# isp.net
KiCad netlist of a schematic drawn in EAGLE
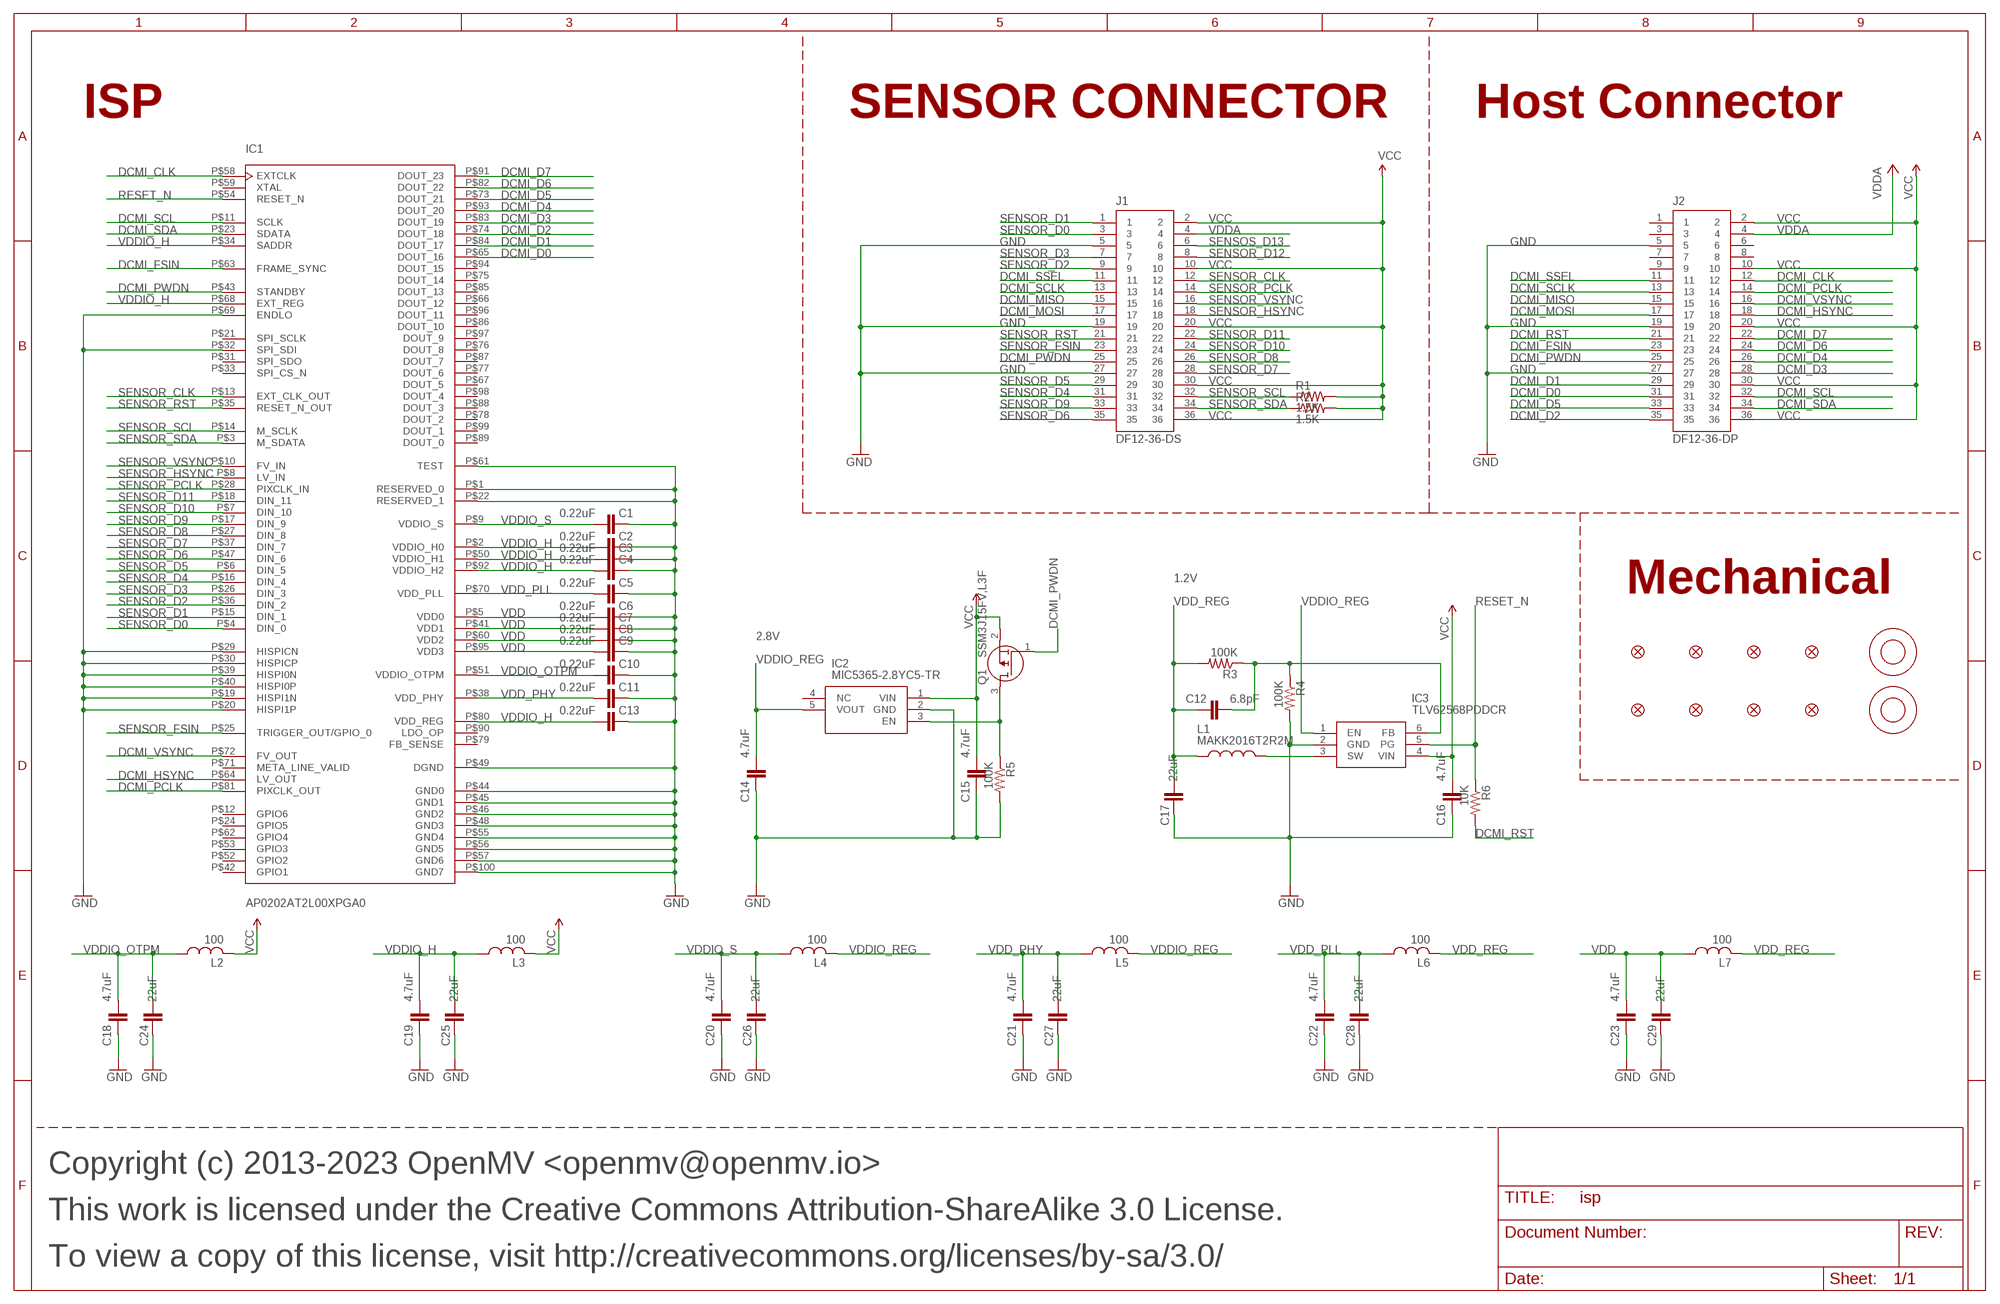
[diagram p0: schematic, sheet 1]

(export (version "E")
  (design (tool "Eeschema 10.0.6"))
  (components
    (comp (ref "C1")
      (value "0.22uF")
      (footprint "eagle-import:C0201")
      (fields (field (name "MPN") "GRM033R60J224ME15D"))
      (libsource (lib "eagle-import") (part "C-EUC0201"))
    )
    (comp (ref "C2")
      (value "0.22uF")
      (footprint "eagle-import:C0201")
      (fields (field (name "MPN") "GRM033R60J224ME15D"))
      (libsource (lib "eagle-import") (part "C-EUC0201"))
    )
    (comp (ref "C3")
      (value "0.22uF")
      (footprint "eagle-import:C0201")
      (fields (field (name "MPN") "GRM033R60J224ME15D"))
      (libsource (lib "eagle-import") (part "C-EUC0201"))
    )
    (comp (ref "C4")
      (value "0.22uF")
      (footprint "eagle-import:C0201")
      (fields (field (name "MPN") "GRM033R60J224ME15D"))
      (libsource (lib "eagle-import") (part "C-EUC0201"))
    )
    (comp (ref "C5")
      (value "0.22uF")
      (footprint "eagle-import:C0201")
      (fields (field (name "MPN") "GRM033R60J224ME15D"))
      (libsource (lib "eagle-import") (part "C-EUC0201"))
    )
    (comp (ref "C6")
      (value "0.22uF")
      (footprint "eagle-import:C0201")
      (fields (field (name "MPN") "GRM033R60J224ME15D"))
      (libsource (lib "eagle-import") (part "C-EUC0201"))
    )
    (comp (ref "C7")
      (value "0.22uF")
      (footprint "eagle-import:C0201")
      (fields (field (name "MPN") "GRM033R60J224ME15D"))
      (libsource (lib "eagle-import") (part "C-EUC0201"))
    )
    (comp (ref "C8")
      (value "0.22uF")
      (footprint "eagle-import:C0201")
      (fields (field (name "MPN") "GRM033R60J224ME15D"))
      (libsource (lib "eagle-import") (part "C-EUC0201"))
    )
    (comp (ref "C9")
      (value "0.22uF")
      (footprint "eagle-import:C0201")
      (fields (field (name "MPN") "GRM033R60J224ME15D"))
      (libsource (lib "eagle-import") (part "C-EUC0201"))
    )
    (comp (ref "C10")
      (value "0.22uF")
      (footprint "eagle-import:C0201")
      (fields (field (name "MPN") "GRM033R60J224ME15D"))
      (libsource (lib "eagle-import") (part "C-EUC0201"))
    )
    (comp (ref "C11")
      (value "0.22uF")
      (footprint "eagle-import:C0201")
      (fields (field (name "MPN") "GRM033R60J224ME15D"))
      (libsource (lib "eagle-import") (part "C-EUC0201"))
    )
    (comp (ref "C12")
      (value "6.8pF")
      (footprint "eagle-import:0402")
      (fields (field (name "MPN") "GRM1555C1H6R8DA01D"))
      (libsource (lib "eagle-import") (part "CAP_0402"))
    )
    (comp (ref "C13")
      (value "0.22uF")
      (footprint "eagle-import:C0201")
      (fields (field (name "MPN") "GRM033R60J224ME15D"))
      (libsource (lib "eagle-import") (part "C-EUC0201"))
    )
    (comp (ref "C14")
      (value "4.7uF")
      (footprint "eagle-import:0402")
      (fields (field (name "MPN") "JMK105BBJ475MV-F"))
      (libsource (lib "eagle-import") (part "CAP_0402"))
    )
    (comp (ref "C15")
      (value "4.7uF")
      (footprint "eagle-import:0402")
      (fields (field (name "MPN") "JMK105BBJ475MV-F"))
      (libsource (lib "eagle-import") (part "CAP_0402"))
    )
    (comp (ref "C16")
      (value "4.7uF")
      (footprint "eagle-import:0402")
      (fields (field (name "MPN") "JMK105BBJ475MV-F"))
      (libsource (lib "eagle-import") (part "CAP_0402"))
    )
    (comp (ref "C17")
      (value "22uF")
      (footprint "eagle-import:0805")
      (fields (field (name "MPN") "CL21A226MQQNNNE"))
      (libsource (lib "eagle-import") (part "22UF-0805-6.3V-20%"))
    )
    (comp (ref "C18")
      (value "4.7uF")
      (footprint "eagle-import:0402")
      (fields (field (name "MPN") "JMK105BBJ475MV-F"))
      (libsource (lib "eagle-import") (part "CAP_0402"))
    )
    (comp (ref "C19")
      (value "4.7uF")
      (footprint "eagle-import:0402")
      (fields (field (name "MPN") "JMK105BBJ475MV-F"))
      (libsource (lib "eagle-import") (part "CAP_0402"))
    )
    (comp (ref "C20")
      (value "4.7uF")
      (footprint "eagle-import:0402")
      (fields (field (name "MPN") "JMK105BBJ475MV-F"))
      (libsource (lib "eagle-import") (part "CAP_0402"))
    )
    (comp (ref "C21")
      (value "4.7uF")
      (footprint "eagle-import:0402")
      (fields (field (name "MPN") "JMK105BBJ475MV-F"))
      (libsource (lib "eagle-import") (part "CAP_0402"))
    )
    (comp (ref "C22")
      (value "4.7uF")
      (footprint "eagle-import:0402")
      (fields (field (name "MPN") "JMK105BBJ475MV-F"))
      (libsource (lib "eagle-import") (part "CAP_0402"))
    )
    (comp (ref "C23")
      (value "4.7uF")
      (footprint "eagle-import:0402")
      (fields (field (name "MPN") "JMK105BBJ475MV-F"))
      (libsource (lib "eagle-import") (part "CAP_0402"))
    )
    (comp (ref "C24")
      (value "22uF")
      (footprint "eagle-import:0805")
      (fields (field (name "MPN") "CL21A226MQQNNNE"))
      (libsource (lib "eagle-import") (part "22UF-0805-6.3V-20%"))
    )
    (comp (ref "C25")
      (value "22uF")
      (footprint "eagle-import:0805")
      (fields (field (name "MPN") "CL21A226MQQNNNE"))
      (libsource (lib "eagle-import") (part "22UF-0805-6.3V-20%"))
    )
    (comp (ref "C26")
      (value "22uF")
      (footprint "eagle-import:0805")
      (fields (field (name "MPN") "CL21A226MQQNNNE"))
      (libsource (lib "eagle-import") (part "22UF-0805-6.3V-20%"))
    )
    (comp (ref "C27")
      (value "22uF")
      (footprint "eagle-import:0805")
      (fields (field (name "MPN") "CL21A226MQQNNNE"))
      (libsource (lib "eagle-import") (part "22UF-0805-6.3V-20%"))
    )
    (comp (ref "C28")
      (value "22uF")
      (footprint "eagle-import:0805")
      (fields (field (name "MPN") "CL21A226MQQNNNE"))
      (libsource (lib "eagle-import") (part "22UF-0805-6.3V-20%"))
    )
    (comp (ref "C29")
      (value "22uF")
      (footprint "eagle-import:0805")
      (fields (field (name "MPN") "CL21A226MQQNNNE"))
      (libsource (lib "eagle-import") (part "22UF-0805-6.3V-20%"))
    )
    (comp (ref "FD1")
      (value "FIDUCIAL1X2")
      (footprint "eagle-import:FIDUCIAL-1X2")
      (libsource (lib "eagle-import") (part "FIDUCIAL1X2"))
    )
    (comp (ref "FD2")
      (value "FIDUCIAL1X2")
      (footprint "eagle-import:FIDUCIAL-1X2")
      (libsource (lib "eagle-import") (part "FIDUCIAL1X2"))
    )
    (comp (ref "FD3")
      (value "FIDUCIAL1X2")
      (footprint "eagle-import:FIDUCIAL-1X2")
      (libsource (lib "eagle-import") (part "FIDUCIAL1X2"))
    )
    (comp (ref "FD4")
      (value "FIDUCIAL1X2")
      (footprint "eagle-import:FIDUCIAL-1X2")
      (libsource (lib "eagle-import") (part "FIDUCIAL1X2"))
    )
    (comp (ref "FD5")
      (value "FIDUCIAL1X2")
      (footprint "eagle-import:FIDUCIAL-1X2")
      (libsource (lib "eagle-import") (part "FIDUCIAL1X2"))
    )
    (comp (ref "FD6")
      (value "FIDUCIAL1X2")
      (footprint "eagle-import:FIDUCIAL-1X2")
      (libsource (lib "eagle-import") (part "FIDUCIAL1X2"))
    )
    (comp (ref "FD7")
      (value "FIDUCIAL1X2")
      (footprint "eagle-import:FIDUCIAL-1X2")
      (libsource (lib "eagle-import") (part "FIDUCIAL1X2"))
    )
    (comp (ref "FD8")
      (value "FIDUCIAL1X2")
      (footprint "eagle-import:FIDUCIAL-1X2")
      (libsource (lib "eagle-import") (part "FIDUCIAL1X2"))
    )
    (comp (ref "IC1")
      (value "AP0202AT2L00XPGA0")
      (footprint "eagle-import:AP0202AT2L00XPGA0")
      (fields (field (name "MPN") "AP0202AT2L00XPGA0-DR"))
      (libsource (lib "eagle-import") (part "AP0202AT2L00XPGA0"))
    )
    (comp (ref "IC2")
      (value "MIC5365-2.8YC5-TR")
      (footprint "eagle-import:SOT65P210X110-5N")
      (fields (field (name "MOUSER_PART_NUMBER") "998-MIC5365-2.8YC5TR"))
      (libsource (lib "eagle-import") (part "MIC5365-2.8YC5-TR"))
    )
    (comp (ref "IC3")
      (value "TLV62568PDDCR")
      (footprint "eagle-import:SOT95P280X110-6N")
      (fields (field (name "MOUSER_PART_NUMBER") "595-TLV62568PDDCR"))
      (libsource (lib "eagle-import") (part "TLV62568PDDCR"))
    )
    (comp (ref "J1")
      (value "DF12-36-DS")
      (footprint "eagle-import:DF12-36-DS")
      (fields (field (name "MPN") "DF12NB(3.0)-36DS-0.5V(51)"))
      (libsource (lib "eagle-import") (part "DF12-36-DS"))
    )
    (comp (ref "J2")
      (value "DF12-36-DP")
      (footprint "eagle-import:DF12-36-DP")
      (fields (field (name "MPN") "DF12NB(3.0)-36DP-0.5V(51)"))
      (libsource (lib "eagle-import") (part "DF12-36-DP"))
    )
    (comp (ref "L1")
      (value "MAKK2016T2R2M")
      (footprint "eagle-import:INDC2016X100N")
      (fields (field (name "MF") "Taiyo Yuden"))
      (libsource (lib "eagle-import") (part "MAKK2016T2R2M"))
    )
    (comp (ref "L2")
      (value "100")
      (footprint "eagle-import:0402")
      (fields (field (name "MPN") "MFBM1V1005-101-R"))
      (libsource (lib "eagle-import") (part "INDUCTOR_0402"))
    )
    (comp (ref "L3")
      (value "100")
      (footprint "eagle-import:0402")
      (fields (field (name "MPN") "MFBM1V1005-101-R"))
      (libsource (lib "eagle-import") (part "INDUCTOR_0402"))
    )
    (comp (ref "L4")
      (value "100")
      (footprint "eagle-import:0402")
      (fields (field (name "MPN") "MFBM1V1005-101-R"))
      (libsource (lib "eagle-import") (part "INDUCTOR_0402"))
    )
    (comp (ref "L5")
      (value "100")
      (footprint "eagle-import:0402")
      (fields (field (name "MPN") "MFBM1V1005-101-R"))
      (libsource (lib "eagle-import") (part "INDUCTOR_0402"))
    )
    (comp (ref "L6")
      (value "100")
      (footprint "eagle-import:0402")
      (fields (field (name "MPN") "MFBM1V1005-101-R"))
      (libsource (lib "eagle-import") (part "INDUCTOR_0402"))
    )
    (comp (ref "L7")
      (value "100")
      (footprint "eagle-import:0402")
      (fields (field (name "MPN") "MFBM1V1005-101-R"))
      (libsource (lib "eagle-import") (part "INDUCTOR_0402"))
    )
    (comp (ref "M1")
      (value "9774030151R")
      (footprint "eagle-import:9774030151R")
      (libsource (lib "eagle-import") (part "9774030151R"))
    )
    (comp (ref "M2")
      (value "9774030151R")
      (footprint "eagle-import:9774030151R")
      (libsource (lib "eagle-import") (part "9774030151R"))
    )
    (comp (ref "Q1")
      (value "SSM3J15FV,L3F")
      (footprint "eagle-import:SSM3J15FVL3F")
      (fields (field (name "MOUSER_PART_NUMBER") "757-SSM3J15FVL3F"))
      (libsource (lib "eagle-import") (part "SSM3J15FV,L3F"))
    )
    (comp (ref "R1")
      (value "1.5K")
      (footprint "eagle-import:R0402")
      (fields (field (name "MPN") "RC0402FR-131K5L"))
      (libsource (lib "eagle-import") (part "R-US_R0402"))
    )
    (comp (ref "R2")
      (value "1.5K")
      (footprint "eagle-import:R0402")
      (fields (field (name "MPN") "RC0402FR-131K5L"))
      (libsource (lib "eagle-import") (part "R-US_R0402"))
    )
    (comp (ref "R3")
      (value "100K")
      (footprint "eagle-import:R0402")
      (fields (field (name "MPN") "AC0402FR-07100KL"))
      (libsource (lib "eagle-import") (part "R-US_R0402"))
    )
    (comp (ref "R4")
      (value "100K")
      (footprint "eagle-import:R0402")
      (fields (field (name "MPN") "AC0402FR-07100KL"))
      (libsource (lib "eagle-import") (part "R-US_R0402"))
    )
    (comp (ref "R5")
      (value "100K")
      (footprint "eagle-import:R0402")
      (fields (field (name "MPN") "AC0402FR-07100KL"))
      (libsource (lib "eagle-import") (part "R-US_R0402"))
    )
    (comp (ref "R6")
      (value "10K")
      (footprint "eagle-import:R0402")
      (fields (field (name "MPN") "AC0402FR-1310KL"))
      (libsource (lib "eagle-import") (part "R-US_R0402"))
    )
  )
  (nets
    (net (code "1") (name "/DCMI_CLK") (class "Default")
      (node (ref "IC1") (pin "P$58") (pinfunction "EXTCLK_P$58") (pintype "input"))
      (node (ref "J2") (pin "12") (pinfunction "12_12") (pintype "bidirectional"))
    )
    (net (code "2") (name "/DCMI_D0") (class "Default")
      (node (ref "IC1") (pin "P$65") (pinfunction "DOUT_16_P$65") (pintype "output"))
      (node (ref "J2") (pin "31") (pinfunction "31_31") (pintype "bidirectional"))
    )
    (net (code "3") (name "/DCMI_D1") (class "Default")
      (node (ref "IC1") (pin "P$84") (pinfunction "DOUT_17_P$84") (pintype "output"))
      (node (ref "J2") (pin "29") (pinfunction "29_29") (pintype "bidirectional"))
    )
    (net (code "4") (name "/DCMI_D2") (class "Default")
      (node (ref "IC1") (pin "P$74") (pinfunction "DOUT_18_P$74") (pintype "output"))
      (node (ref "J2") (pin "35") (pinfunction "35_35") (pintype "bidirectional"))
    )
    (net (code "5") (name "/DCMI_D3") (class "Default")
      (node (ref "IC1") (pin "P$83") (pinfunction "DOUT_19_P$83") (pintype "output"))
      (node (ref "J2") (pin "28") (pinfunction "28_28") (pintype "bidirectional"))
    )
    (net (code "6") (name "/DCMI_D4") (class "Default")
      (node (ref "IC1") (pin "P$93") (pinfunction "DOUT_20_P$93") (pintype "output"))
      (node (ref "J2") (pin "26") (pinfunction "26_26") (pintype "bidirectional"))
    )
    (net (code "7") (name "/DCMI_D5") (class "Default")
      (node (ref "IC1") (pin "P$73") (pinfunction "DOUT_21_P$73") (pintype "output"))
      (node (ref "J2") (pin "33") (pinfunction "33_33") (pintype "bidirectional"))
    )
    (net (code "8") (name "/DCMI_D6") (class "Default")
      (node (ref "IC1") (pin "P$82") (pinfunction "DOUT_22_P$82") (pintype "output"))
      (node (ref "J2") (pin "24") (pinfunction "24_24") (pintype "bidirectional"))
    )
    (net (code "9") (name "/DCMI_D7") (class "Default")
      (node (ref "IC1") (pin "P$91") (pinfunction "DOUT_23_P$91") (pintype "output"))
      (node (ref "J2") (pin "22") (pinfunction "22_22") (pintype "bidirectional"))
    )
    (net (code "10") (name "/DCMI_FSIN") (class "Default")
      (node (ref "IC1") (pin "P$63") (pinfunction "FRAME_SYNC_P$63") (pintype "input"))
      (node (ref "J2") (pin "23") (pinfunction "23_23") (pintype "bidirectional"))
    )
    (net (code "11") (name "/DCMI_HSYNC") (class "Default")
      (node (ref "IC1") (pin "P$64") (pinfunction "LV_OUT_P$64") (pintype "output"))
      (node (ref "J2") (pin "18") (pinfunction "18_18") (pintype "bidirectional"))
    )
    (net (code "12") (name "/DCMI_MISO") (class "Default")
      (node (ref "J1") (pin "15") (pinfunction "15_15") (pintype "bidirectional"))
      (node (ref "J2") (pin "15") (pinfunction "15_15") (pintype "bidirectional"))
    )
    (net (code "13") (name "/DCMI_MOSI") (class "Default")
      (node (ref "J1") (pin "17") (pinfunction "17_17") (pintype "bidirectional"))
      (node (ref "J2") (pin "17") (pinfunction "17_17") (pintype "bidirectional"))
    )
    (net (code "14") (name "/DCMI_PCLK") (class "Default")
      (node (ref "IC1") (pin "P$81") (pinfunction "PIXCLK_OUT_P$81") (pintype "output"))
      (node (ref "J2") (pin "14") (pinfunction "14_14") (pintype "bidirectional"))
    )
    (net (code "15") (name "/DCMI_PWDN") (class "Default")
      (node (ref "IC1") (pin "P$43") (pinfunction "STANDBY_P$43") (pintype "input"))
      (node (ref "J1") (pin "25") (pinfunction "25_25") (pintype "bidirectional"))
      (node (ref "J2") (pin "25") (pinfunction "25_25") (pintype "bidirectional"))
      (node (ref "Q1") (pin "1") (pinfunction "G_1") (pintype "bidirectional"))
    )
    (net (code "16") (name "/DCMI_RST") (class "Default")
      (node (ref "J2") (pin "21") (pinfunction "21_21") (pintype "bidirectional"))
      (node (ref "R6") (pin "2") (pinfunction "2_2") (pintype "passive"))
    )
    (net (code "17") (name "/DCMI_SCL") (class "Default")
      (node (ref "IC1") (pin "P$11") (pinfunction "SCLK_P$11") (pintype "input"))
      (node (ref "J2") (pin "32") (pinfunction "32_32") (pintype "bidirectional"))
    )
    (net (code "18") (name "/DCMI_SCLK") (class "Default")
      (node (ref "J1") (pin "13") (pinfunction "13_13") (pintype "bidirectional"))
      (node (ref "J2") (pin "13") (pinfunction "13_13") (pintype "bidirectional"))
    )
    (net (code "19") (name "/DCMI_SDA") (class "Default")
      (node (ref "IC1") (pin "P$23") (pinfunction "SDATA_P$23") (pintype "bidirectional"))
      (node (ref "J2") (pin "34") (pinfunction "34_34") (pintype "bidirectional"))
    )
    (net (code "20") (name "/DCMI_SSEL") (class "Default")
      (node (ref "J1") (pin "11") (pinfunction "11_11") (pintype "bidirectional"))
      (node (ref "J2") (pin "11") (pinfunction "11_11") (pintype "bidirectional"))
    )
    (net (code "21") (name "/DCMI_VSYNC") (class "Default")
      (node (ref "IC1") (pin "P$72") (pinfunction "FV_OUT_P$72") (pintype "output"))
      (node (ref "J2") (pin "16") (pinfunction "16_16") (pintype "bidirectional"))
    )
    (net (code "22") (name "/RESET_N") (class "Default")
      (node (ref "IC1") (pin "P$54") (pinfunction "RESET_N_P$54") (pintype "input"))
      (node (ref "IC3") (pin "5") (pinfunction "PG_5") (pintype "bidirectional"))
      (node (ref "R6") (pin "1") (pinfunction "1_1") (pintype "passive"))
    )
    (net (code "23") (name "/SENSOR_CLK") (class "Default")
      (node (ref "IC1") (pin "P$13") (pinfunction "EXT_CLK_OUT_P$13") (pintype "output"))
      (node (ref "J1") (pin "12") (pinfunction "12_12") (pintype "bidirectional"))
    )
    (net (code "24") (name "/SENSOR_D0") (class "Default")
      (node (ref "IC1") (pin "P$4") (pinfunction "DIN_0_P$4") (pintype "input"))
      (node (ref "J1") (pin "3") (pinfunction "3_3") (pintype "bidirectional"))
    )
    (net (code "25") (name "/SENSOR_D1") (class "Default")
      (node (ref "IC1") (pin "P$15") (pinfunction "DIN_1_P$15") (pintype "input"))
      (node (ref "J1") (pin "1") (pinfunction "1_1") (pintype "bidirectional"))
    )
    (net (code "26") (name "/SENSOR_D2") (class "Default")
      (node (ref "IC1") (pin "P$36") (pinfunction "DIN_2_P$36") (pintype "input"))
      (node (ref "J1") (pin "9") (pinfunction "9_9") (pintype "bidirectional"))
    )
    (net (code "27") (name "/SENSOR_D3") (class "Default")
      (node (ref "IC1") (pin "P$26") (pinfunction "DIN_3_P$26") (pintype "input"))
      (node (ref "J1") (pin "7") (pinfunction "7_7") (pintype "bidirectional"))
    )
    (net (code "28") (name "/SENSOR_D4") (class "Default")
      (node (ref "IC1") (pin "P$16") (pinfunction "DIN_4_P$16") (pintype "input"))
      (node (ref "J1") (pin "31") (pinfunction "31_31") (pintype "bidirectional"))
    )
    (net (code "29") (name "/SENSOR_D5") (class "Default")
      (node (ref "IC1") (pin "P$6") (pinfunction "DIN_5_P$6") (pintype "input"))
      (node (ref "J1") (pin "29") (pinfunction "29_29") (pintype "bidirectional"))
    )
    (net (code "30") (name "/SENSOR_D6") (class "Default")
      (node (ref "IC1") (pin "P$47") (pinfunction "DIN_6_P$47") (pintype "input"))
      (node (ref "J1") (pin "35") (pinfunction "35_35") (pintype "bidirectional"))
    )
    (net (code "31") (name "/SENSOR_D7") (class "Default")
      (node (ref "IC1") (pin "P$37") (pinfunction "DIN_7_P$37") (pintype "input"))
      (node (ref "J1") (pin "28") (pinfunction "28_28") (pintype "bidirectional"))
    )
    (net (code "32") (name "/SENSOR_D8") (class "Default")
      (node (ref "IC1") (pin "P$27") (pinfunction "DIN_8_P$27") (pintype "input"))
      (node (ref "J1") (pin "26") (pinfunction "26_26") (pintype "bidirectional"))
    )
    (net (code "33") (name "/SENSOR_D9") (class "Default")
      (node (ref "IC1") (pin "P$17") (pinfunction "DIN_9_P$17") (pintype "input"))
      (node (ref "J1") (pin "33") (pinfunction "33_33") (pintype "bidirectional"))
    )
    (net (code "34") (name "/SENSOR_D10") (class "Default")
      (node (ref "IC1") (pin "P$7") (pinfunction "DIN_10_P$7") (pintype "input"))
      (node (ref "J1") (pin "24") (pinfunction "24_24") (pintype "bidirectional"))
    )
    (net (code "35") (name "/SENSOR_D11") (class "Default")
      (node (ref "IC1") (pin "P$18") (pinfunction "DIN_11_P$18") (pintype "input"))
      (node (ref "J1") (pin "22") (pinfunction "22_22") (pintype "bidirectional"))
    )
    (net (code "36") (name "/SENSOR_D12") (class "Default")
      (node (ref "J1") (pin "8") (pinfunction "8_8") (pintype "bidirectional"))
    )
    (net (code "37") (name "/SENSOR_FSIN") (class "Default")
      (node (ref "IC1") (pin "P$25") (pinfunction "TRIGGER_OUT/GPIO_0_P$25") (pintype "output"))
      (node (ref "J1") (pin "23") (pinfunction "23_23") (pintype "bidirectional"))
    )
    (net (code "38") (name "/SENSOR_HSYNC") (class "Default")
      (node (ref "IC1") (pin "P$8") (pinfunction "LV_IN_P$8") (pintype "input"))
      (node (ref "J1") (pin "18") (pinfunction "18_18") (pintype "bidirectional"))
    )
    (net (code "39") (name "/SENSOR_PCLK") (class "Default")
      (node (ref "IC1") (pin "P$28") (pinfunction "PIXCLK_IN_P$28") (pintype "input"))
      (node (ref "J1") (pin "14") (pinfunction "14_14") (pintype "bidirectional"))
    )
    (net (code "40") (name "/SENSOR_RST") (class "Default")
      (node (ref "IC1") (pin "P$35") (pinfunction "RESET_N_OUT_P$35") (pintype "output"))
      (node (ref "J1") (pin "21") (pinfunction "21_21") (pintype "bidirectional"))
    )
    (net (code "41") (name "/SENSOR_SCL") (class "Default")
      (node (ref "IC1") (pin "P$14") (pinfunction "M_SCLK_P$14") (pintype "output"))
      (node (ref "J1") (pin "32") (pinfunction "32_32") (pintype "bidirectional"))
      (node (ref "R1") (pin "1") (pinfunction "1_1") (pintype "passive"))
    )
    (net (code "42") (name "/SENSOR_SDA") (class "Default")
      (node (ref "IC1") (pin "P$3") (pinfunction "M_SDATA_P$3") (pintype "bidirectional"))
      (node (ref "J1") (pin "34") (pinfunction "34_34") (pintype "bidirectional"))
      (node (ref "R2") (pin "1") (pinfunction "1_1") (pintype "passive"))
    )
    (net (code "43") (name "/SENSOR_VSYNC") (class "Default")
      (node (ref "IC1") (pin "P$10") (pinfunction "FV_IN_P$10") (pintype "input"))
      (node (ref "J1") (pin "16") (pinfunction "16_16") (pintype "bidirectional"))
    )
    (net (code "44") (name "/SENSOS_D13") (class "Default")
      (node (ref "J1") (pin "6") (pinfunction "6_6") (pintype "bidirectional"))
    )
    (net (code "45") (name "/VDD") (class "Default")
      (node (ref "C23") (pin "2") (pinfunction "2_2") (pintype "passive"))
      (node (ref "C29") (pin "2") (pinfunction "2_2") (pintype "passive"))
      (node (ref "C6") (pin "2") (pinfunction "2_2") (pintype "passive"))
      (node (ref "C7") (pin "2") (pinfunction "2_2") (pintype "passive"))
      (node (ref "C8") (pin "2") (pinfunction "2_2") (pintype "passive"))
      (node (ref "C9") (pin "2") (pinfunction "2_2") (pintype "passive"))
      (node (ref "IC1") (pin "P$41") (pinfunction "VDD1_P$41") (pintype "power_in"))
      (node (ref "IC1") (pin "P$5") (pinfunction "VDD0_P$5") (pintype "power_in"))
      (node (ref "IC1") (pin "P$60") (pinfunction "VDD2_P$60") (pintype "power_in"))
      (node (ref "IC1") (pin "P$95") (pinfunction "VDD3_P$95") (pintype "power_in"))
      (node (ref "L7") (pin "1") (pinfunction "P$1_1") (pintype "passive"))
    )
    (net (code "46") (name "/VDDIO_H") (class "Default")
      (node (ref "C13") (pin "2") (pinfunction "2_2") (pintype "passive"))
      (node (ref "C19") (pin "2") (pinfunction "2_2") (pintype "passive"))
      (node (ref "C2") (pin "2") (pinfunction "2_2") (pintype "passive"))
      (node (ref "C25") (pin "2") (pinfunction "2_2") (pintype "passive"))
      (node (ref "C3") (pin "2") (pinfunction "2_2") (pintype "passive"))
      (node (ref "C4") (pin "2") (pinfunction "2_2") (pintype "passive"))
      (node (ref "IC1") (pin "P$2") (pinfunction "VDDIO_H0_P$2") (pintype "power_in"))
      (node (ref "IC1") (pin "P$34") (pinfunction "SADDR_P$34") (pintype "input"))
      (node (ref "IC1") (pin "P$50") (pinfunction "VDDIO_H1_P$50") (pintype "power_in"))
      (node (ref "IC1") (pin "P$68") (pinfunction "EXT_REG_P$68") (pintype "input"))
      (node (ref "IC1") (pin "P$80") (pinfunction "VDD_REG_P$80") (pintype "power_in"))
      (node (ref "IC1") (pin "P$92") (pinfunction "VDDIO_H2_P$92") (pintype "power_in"))
      (node (ref "L3") (pin "1") (pinfunction "P$1_1") (pintype "passive"))
    )
    (net (code "47") (name "/VDDIO_OTPM") (class "Default")
      (node (ref "C10") (pin "2") (pinfunction "2_2") (pintype "passive"))
      (node (ref "C18") (pin "2") (pinfunction "2_2") (pintype "passive"))
      (node (ref "C24") (pin "2") (pinfunction "2_2") (pintype "passive"))
      (node (ref "IC1") (pin "P$51") (pinfunction "VDDIO_OTPM_P$51") (pintype "power_in"))
      (node (ref "L2") (pin "1") (pinfunction "P$1_1") (pintype "passive"))
    )
    (net (code "48") (name "/VDDIO_REG") (class "Default")
      (node (ref "C14") (pin "2") (pinfunction "2_2") (pintype "passive"))
      (node (ref "IC2") (pin "5") (pinfunction "VOUT_5") (pintype "bidirectional"))
      (node (ref "IC3") (pin "1") (pinfunction "EN_1") (pintype "bidirectional"))
      (node (ref "L4") (pin "2") (pinfunction "P$2_2") (pintype "passive"))
      (node (ref "L5") (pin "2") (pinfunction "P$2_2") (pintype "passive"))
    )
    (net (code "49") (name "/VDDIO_S") (class "Default")
      (node (ref "C1") (pin "2") (pinfunction "2_2") (pintype "passive"))
      (node (ref "C20") (pin "2") (pinfunction "2_2") (pintype "passive"))
      (node (ref "C26") (pin "2") (pinfunction "2_2") (pintype "passive"))
      (node (ref "IC1") (pin "P$9") (pinfunction "VDDIO_S_P$9") (pintype "power_in"))
      (node (ref "L4") (pin "1") (pinfunction "P$1_1") (pintype "passive"))
    )
    (net (code "50") (name "/VDD_PHY") (class "Default")
      (node (ref "C11") (pin "2") (pinfunction "2_2") (pintype "passive"))
      (node (ref "C21") (pin "2") (pinfunction "2_2") (pintype "passive"))
      (node (ref "C27") (pin "2") (pinfunction "2_2") (pintype "passive"))
      (node (ref "IC1") (pin "P$38") (pinfunction "VDD_PHY_P$38") (pintype "power_in"))
      (node (ref "L5") (pin "1") (pinfunction "P$1_1") (pintype "passive"))
    )
    (net (code "51") (name "/VDD_PLL") (class "Default")
      (node (ref "C22") (pin "2") (pinfunction "2_2") (pintype "passive"))
      (node (ref "C28") (pin "2") (pinfunction "2_2") (pintype "passive"))
      (node (ref "C5") (pin "2") (pinfunction "2_2") (pintype "passive"))
      (node (ref "IC1") (pin "P$70") (pinfunction "VDD_PLL_P$70") (pintype "power_in"))
      (node (ref "L6") (pin "1") (pinfunction "P$1_1") (pintype "passive"))
    )
    (net (code "52") (name "/VDD_REG") (class "Default")
      (node (ref "C12") (pin "1") (pinfunction "1_1") (pintype "passive"))
      (node (ref "C17") (pin "2") (pinfunction "2_2") (pintype "passive"))
      (node (ref "L1") (pin "1") (pinfunction "1_1") (pintype "passive"))
      (node (ref "L6") (pin "2") (pinfunction "P$2_2") (pintype "passive"))
      (node (ref "L7") (pin "2") (pinfunction "P$2_2") (pintype "passive"))
      (node (ref "R3") (pin "2") (pinfunction "2_2") (pintype "passive"))
    )
    (net (code "53") (name "GND") (class "Default")
      (node (ref "C1") (pin "1") (pinfunction "1_1") (pintype "passive"))
      (node (ref "C10") (pin "1") (pinfunction "1_1") (pintype "passive"))
      (node (ref "C11") (pin "1") (pinfunction "1_1") (pintype "passive"))
      (node (ref "C13") (pin "1") (pinfunction "1_1") (pintype "passive"))
      (node (ref "C14") (pin "1") (pinfunction "1_1") (pintype "passive"))
      (node (ref "C15") (pin "1") (pinfunction "1_1") (pintype "passive"))
      (node (ref "C16") (pin "1") (pinfunction "1_1") (pintype "passive"))
      (node (ref "C17") (pin "1") (pinfunction "1_1") (pintype "passive"))
      (node (ref "C18") (pin "1") (pinfunction "1_1") (pintype "passive"))
      (node (ref "C19") (pin "1") (pinfunction "1_1") (pintype "passive"))
      (node (ref "C2") (pin "1") (pinfunction "1_1") (pintype "passive"))
      (node (ref "C20") (pin "1") (pinfunction "1_1") (pintype "passive"))
      (node (ref "C21") (pin "1") (pinfunction "1_1") (pintype "passive"))
      (node (ref "C22") (pin "1") (pinfunction "1_1") (pintype "passive"))
      (node (ref "C23") (pin "1") (pinfunction "1_1") (pintype "passive"))
      (node (ref "C24") (pin "1") (pinfunction "1_1") (pintype "passive"))
      (node (ref "C25") (pin "1") (pinfunction "1_1") (pintype "passive"))
      (node (ref "C26") (pin "1") (pinfunction "1_1") (pintype "passive"))
      (node (ref "C27") (pin "1") (pinfunction "1_1") (pintype "passive"))
      (node (ref "C28") (pin "1") (pinfunction "1_1") (pintype "passive"))
      (node (ref "C29") (pin "1") (pinfunction "1_1") (pintype "passive"))
      (node (ref "C3") (pin "1") (pinfunction "1_1") (pintype "passive"))
      (node (ref "C4") (pin "1") (pinfunction "1_1") (pintype "passive"))
      (node (ref "C5") (pin "1") (pinfunction "1_1") (pintype "passive"))
      (node (ref "C6") (pin "1") (pinfunction "1_1") (pintype "passive"))
      (node (ref "C7") (pin "1") (pinfunction "1_1") (pintype "passive"))
      (node (ref "C8") (pin "1") (pinfunction "1_1") (pintype "passive"))
      (node (ref "C9") (pin "1") (pinfunction "1_1") (pintype "passive"))
      (node (ref "IC1") (pin "P$1") (pinfunction "RESERVED_0_P$1") (pintype "input"))
      (node (ref "IC1") (pin "P$100") (pinfunction "GND7_P$100") (pintype "power_in"))
      (node (ref "IC1") (pin "P$19") (pinfunction "HISPI1N_P$19") (pintype "input"))
      (node (ref "IC1") (pin "P$20") (pinfunction "HISPI1P_P$20") (pintype "input"))
      (node (ref "IC1") (pin "P$22") (pinfunction "RESERVED_1_P$22") (pintype "input"))
      (node (ref "IC1") (pin "P$29") (pinfunction "HISPICN_P$29") (pintype "input"))
      (node (ref "IC1") (pin "P$30") (pinfunction "HISPICP_P$30") (pintype "input"))
      (node (ref "IC1") (pin "P$32") (pinfunction "SPI_SDI_P$32") (pintype "input"))
      (node (ref "IC1") (pin "P$39") (pinfunction "HISPI0N_P$39") (pintype "input"))
      (node (ref "IC1") (pin "P$40") (pinfunction "HISPI0P_P$40") (pintype "input"))
      (node (ref "IC1") (pin "P$44") (pinfunction "GND0_P$44") (pintype "power_in"))
      (node (ref "IC1") (pin "P$45") (pinfunction "GND1_P$45") (pintype "power_in"))
      (node (ref "IC1") (pin "P$46") (pinfunction "GND2_P$46") (pintype "power_in"))
      (node (ref "IC1") (pin "P$48") (pinfunction "GND3_P$48") (pintype "power_in"))
      (node (ref "IC1") (pin "P$49") (pinfunction "DGND_P$49") (pintype "power_in"))
      (node (ref "IC1") (pin "P$55") (pinfunction "GND4_P$55") (pintype "power_in"))
      (node (ref "IC1") (pin "P$56") (pinfunction "GND5_P$56") (pintype "power_in"))
      (node (ref "IC1") (pin "P$57") (pinfunction "GND6_P$57") (pintype "power_in"))
      (node (ref "IC1") (pin "P$61") (pinfunction "TEST_P$61") (pintype "input"))
      (node (ref "IC1") (pin "P$69") (pinfunction "ENDLO_P$69") (pintype "input"))
      (node (ref "IC2") (pin "2") (pinfunction "GND_2") (pintype "bidirectional"))
      (node (ref "IC3") (pin "2") (pinfunction "GND_2") (pintype "bidirectional"))
      (node (ref "J1") (pin "19") (pinfunction "19_19") (pintype "bidirectional"))
      (node (ref "J1") (pin "27") (pinfunction "27_27") (pintype "bidirectional"))
      (node (ref "J1") (pin "5") (pinfunction "5_5") (pintype "bidirectional"))
      (node (ref "J2") (pin "19") (pinfunction "19_19") (pintype "bidirectional"))
      (node (ref "J2") (pin "27") (pinfunction "27_27") (pintype "bidirectional"))
      (node (ref "J2") (pin "5") (pinfunction "5_5") (pintype "bidirectional"))
      (node (ref "R4") (pin "2") (pinfunction "2_2") (pintype "passive"))
      (node (ref "R5") (pin "2") (pinfunction "2_2") (pintype "passive"))
    )
    (net (code "54") (name "Net-(IC2-EN)") (class "Default")
      (node (ref "IC2") (pin "3") (pinfunction "EN_3") (pintype "bidirectional"))
      (node (ref "Q1") (pin "3") (pinfunction "D_3") (pintype "bidirectional"))
      (node (ref "R5") (pin "1") (pinfunction "1_1") (pintype "passive"))
    )
    (net (code "55") (name "Net-(IC3-FB)") (class "Default")
      (node (ref "C12") (pin "2") (pinfunction "2_2") (pintype "passive"))
      (node (ref "IC3") (pin "6") (pinfunction "FB_6") (pintype "bidirectional"))
      (node (ref "R3") (pin "1") (pinfunction "1_1") (pintype "passive"))
      (node (ref "R4") (pin "1") (pinfunction "1_1") (pintype "passive"))
    )
    (net (code "56") (name "Net-(IC3-SW)") (class "Default")
      (node (ref "IC3") (pin "3") (pinfunction "SW_3") (pintype "bidirectional"))
      (node (ref "L1") (pin "2") (pinfunction "2_2") (pintype "passive"))
    )
    (net (code "57") (name "VCC") (class "Default")
      (node (ref "C15") (pin "2") (pinfunction "2_2") (pintype "passive"))
      (node (ref "C16") (pin "2") (pinfunction "2_2") (pintype "passive"))
      (node (ref "IC2") (pin "1") (pinfunction "VIN_1") (pintype "bidirectional"))
      (node (ref "IC3") (pin "4") (pinfunction "VIN_4") (pintype "bidirectional"))
      (node (ref "J1") (pin "10") (pinfunction "10_10") (pintype "bidirectional"))
      (node (ref "J1") (pin "2") (pinfunction "2_2") (pintype "bidirectional"))
      (node (ref "J1") (pin "20") (pinfunction "20_20") (pintype "bidirectional"))
      (node (ref "J1") (pin "30") (pinfunction "30_30") (pintype "bidirectional"))
      (node (ref "J1") (pin "36") (pinfunction "36_36") (pintype "bidirectional"))
      (node (ref "J2") (pin "10") (pinfunction "10_10") (pintype "bidirectional"))
      (node (ref "J2") (pin "2") (pinfunction "2_2") (pintype "bidirectional"))
      (node (ref "J2") (pin "20") (pinfunction "20_20") (pintype "bidirectional"))
      (node (ref "J2") (pin "30") (pinfunction "30_30") (pintype "bidirectional"))
      (node (ref "J2") (pin "36") (pinfunction "36_36") (pintype "bidirectional"))
      (node (ref "L2") (pin "2") (pinfunction "P$2_2") (pintype "passive"))
      (node (ref "L3") (pin "2") (pinfunction "P$2_2") (pintype "passive"))
      (node (ref "Q1") (pin "2") (pinfunction "S_2") (pintype "bidirectional"))
      (node (ref "R1") (pin "2") (pinfunction "2_2") (pintype "passive"))
      (node (ref "R2") (pin "2") (pinfunction "2_2") (pintype "passive"))
    )
    (net (code "58") (name "VDDA") (class "Default")
      (node (ref "J1") (pin "4") (pinfunction "4_4") (pintype "bidirectional"))
      (node (ref "J2") (pin "4") (pinfunction "4_4") (pintype "bidirectional"))
    )
    (net (code "59") (name "unconnected-(IC1-DOUT_0-PadP$89)") (class "Default")
      (node (ref "IC1") (pin "P$89") (pinfunction "DOUT_0_P$89") (pintype "output"))
    )
    (net (code "60") (name "unconnected-(IC1-DOUT_1-PadP$99)") (class "Default")
      (node (ref "IC1") (pin "P$99") (pinfunction "DOUT_1_P$99") (pintype "output"))
    )
    (net (code "61") (name "unconnected-(IC1-DOUT_2-PadP$78)") (class "Default")
      (node (ref "IC1") (pin "P$78") (pinfunction "DOUT_2_P$78") (pintype "output"))
    )
    (net (code "62") (name "unconnected-(IC1-DOUT_3-PadP$88)") (class "Default")
      (node (ref "IC1") (pin "P$88") (pinfunction "DOUT_3_P$88") (pintype "output"))
    )
    (net (code "63") (name "unconnected-(IC1-DOUT_4-PadP$98)") (class "Default")
      (node (ref "IC1") (pin "P$98") (pinfunction "DOUT_4_P$98") (pintype "output"))
    )
    (net (code "64") (name "unconnected-(IC1-DOUT_5-PadP$67)") (class "Default")
      (node (ref "IC1") (pin "P$67") (pinfunction "DOUT_5_P$67") (pintype "output"))
    )
    (net (code "65") (name "unconnected-(IC1-DOUT_6-PadP$77)") (class "Default")
      (node (ref "IC1") (pin "P$77") (pinfunction "DOUT_6_P$77") (pintype "output"))
    )
    (net (code "66") (name "unconnected-(IC1-DOUT_7-PadP$87)") (class "Default")
      (node (ref "IC1") (pin "P$87") (pinfunction "DOUT_7_P$87") (pintype "output"))
    )
    (net (code "67") (name "unconnected-(IC1-DOUT_8-PadP$76)") (class "Default")
      (node (ref "IC1") (pin "P$76") (pinfunction "DOUT_8_P$76") (pintype "output"))
    )
    (net (code "68") (name "unconnected-(IC1-DOUT_9-PadP$97)") (class "Default")
      (node (ref "IC1") (pin "P$97") (pinfunction "DOUT_9_P$97") (pintype "output"))
    )
    (net (code "69") (name "unconnected-(IC1-DOUT_10-PadP$86)") (class "Default")
      (node (ref "IC1") (pin "P$86") (pinfunction "DOUT_10_P$86") (pintype "output"))
    )
    (net (code "70") (name "unconnected-(IC1-DOUT_11-PadP$96)") (class "Default")
      (node (ref "IC1") (pin "P$96") (pinfunction "DOUT_11_P$96") (pintype "output"))
    )
    (net (code "71") (name "unconnected-(IC1-DOUT_12-PadP$66)") (class "Default")
      (node (ref "IC1") (pin "P$66") (pinfunction "DOUT_12_P$66") (pintype "output"))
    )
    (net (code "72") (name "unconnected-(IC1-DOUT_13-PadP$85)") (class "Default")
      (node (ref "IC1") (pin "P$85") (pinfunction "DOUT_13_P$85") (pintype "output"))
    )
    (net (code "73") (name "unconnected-(IC1-DOUT_14-PadP$75)") (class "Default")
      (node (ref "IC1") (pin "P$75") (pinfunction "DOUT_14_P$75") (pintype "output"))
    )
    (net (code "74") (name "unconnected-(IC1-DOUT_15-PadP$94)") (class "Default")
      (node (ref "IC1") (pin "P$94") (pinfunction "DOUT_15_P$94") (pintype "output"))
    )
    (net (code "75") (name "unconnected-(IC1-FB_SENSE-PadP$79)") (class "Default")
      (node (ref "IC1") (pin "P$79") (pinfunction "FB_SENSE_P$79") (pintype "input"))
    )
    (net (code "76") (name "unconnected-(IC1-GPIO1-PadP$42)") (class "Default")
      (node (ref "IC1") (pin "P$42") (pinfunction "GPIO1_P$42") (pintype "bidirectional"))
    )
    (net (code "77") (name "unconnected-(IC1-GPIO2-PadP$52)") (class "Default")
      (node (ref "IC1") (pin "P$52") (pinfunction "GPIO2_P$52") (pintype "bidirectional"))
    )
    (net (code "78") (name "unconnected-(IC1-GPIO3-PadP$53)") (class "Default")
      (node (ref "IC1") (pin "P$53") (pinfunction "GPIO3_P$53") (pintype "bidirectional"))
    )
    (net (code "79") (name "unconnected-(IC1-GPIO4-PadP$62)") (class "Default")
      (node (ref "IC1") (pin "P$62") (pinfunction "GPIO4_P$62") (pintype "bidirectional"))
    )
    (net (code "80") (name "unconnected-(IC1-GPIO5-PadP$24)") (class "Default")
      (node (ref "IC1") (pin "P$24") (pinfunction "GPIO5_P$24") (pintype "bidirectional"))
    )
    (net (code "81") (name "unconnected-(IC1-GPIO6-PadP$12)") (class "Default")
      (node (ref "IC1") (pin "P$12") (pinfunction "GPIO6_P$12") (pintype "bidirectional"))
    )
    (net (code "82") (name "unconnected-(IC1-LDO_OP-PadP$90)") (class "Default")
      (node (ref "IC1") (pin "P$90") (pinfunction "LDO_OP_P$90") (pintype "output"))
    )
    (net (code "83") (name "unconnected-(IC1-META_LINE_VALID-PadP$71)") (class "Default")
      (node (ref "IC1") (pin "P$71") (pinfunction "META_LINE_VALID_P$71") (pintype "output"))
    )
    (net (code "84") (name "unconnected-(IC1-SPI_CS_N-PadP$33)") (class "Default")
      (node (ref "IC1") (pin "P$33") (pinfunction "SPI_CS_N_P$33") (pintype "output"))
    )
    (net (code "85") (name "unconnected-(IC1-SPI_SCLK-PadP$21)") (class "Default")
      (node (ref "IC1") (pin "P$21") (pinfunction "SPI_SCLK_P$21") (pintype "output"))
    )
    (net (code "86") (name "unconnected-(IC1-SPI_SDO-PadP$31)") (class "Default")
      (node (ref "IC1") (pin "P$31") (pinfunction "SPI_SDO_P$31") (pintype "output"))
    )
    (net (code "87") (name "unconnected-(IC1-XTAL-PadP$59)") (class "Default")
      (node (ref "IC1") (pin "P$59") (pinfunction "XTAL_P$59") (pintype "output"))
    )
    (net (code "88") (name "unconnected-(IC2-NC-Pad4)") (class "Default")
      (node (ref "IC2") (pin "4") (pinfunction "NC_4") (pintype "no_connect"))
    )
    (net (code "89") (name "unconnected-(J2-Pad1)") (class "Default")
      (node (ref "J2") (pin "1") (pinfunction "1_1") (pintype "bidirectional"))
    )
    (net (code "90") (name "unconnected-(J2-Pad3)") (class "Default")
      (node (ref "J2") (pin "3") (pinfunction "3_3") (pintype "bidirectional"))
    )
    (net (code "91") (name "unconnected-(J2-Pad6)") (class "Default")
      (node (ref "J2") (pin "6") (pinfunction "6_6") (pintype "bidirectional"))
    )
    (net (code "92") (name "unconnected-(J2-Pad7)") (class "Default")
      (node (ref "J2") (pin "7") (pinfunction "7_7") (pintype "bidirectional"))
    )
    (net (code "93") (name "unconnected-(J2-Pad8)") (class "Default")
      (node (ref "J2") (pin "8") (pinfunction "8_8") (pintype "bidirectional"))
    )
    (net (code "94") (name "unconnected-(J2-Pad9)") (class "Default")
      (node (ref "J2") (pin "9") (pinfunction "9_9") (pintype "bidirectional"))
    )
  )
)
